# Pico_Audio_v0_20.net
KiCad netlist of a schematic drawn in EAGLE
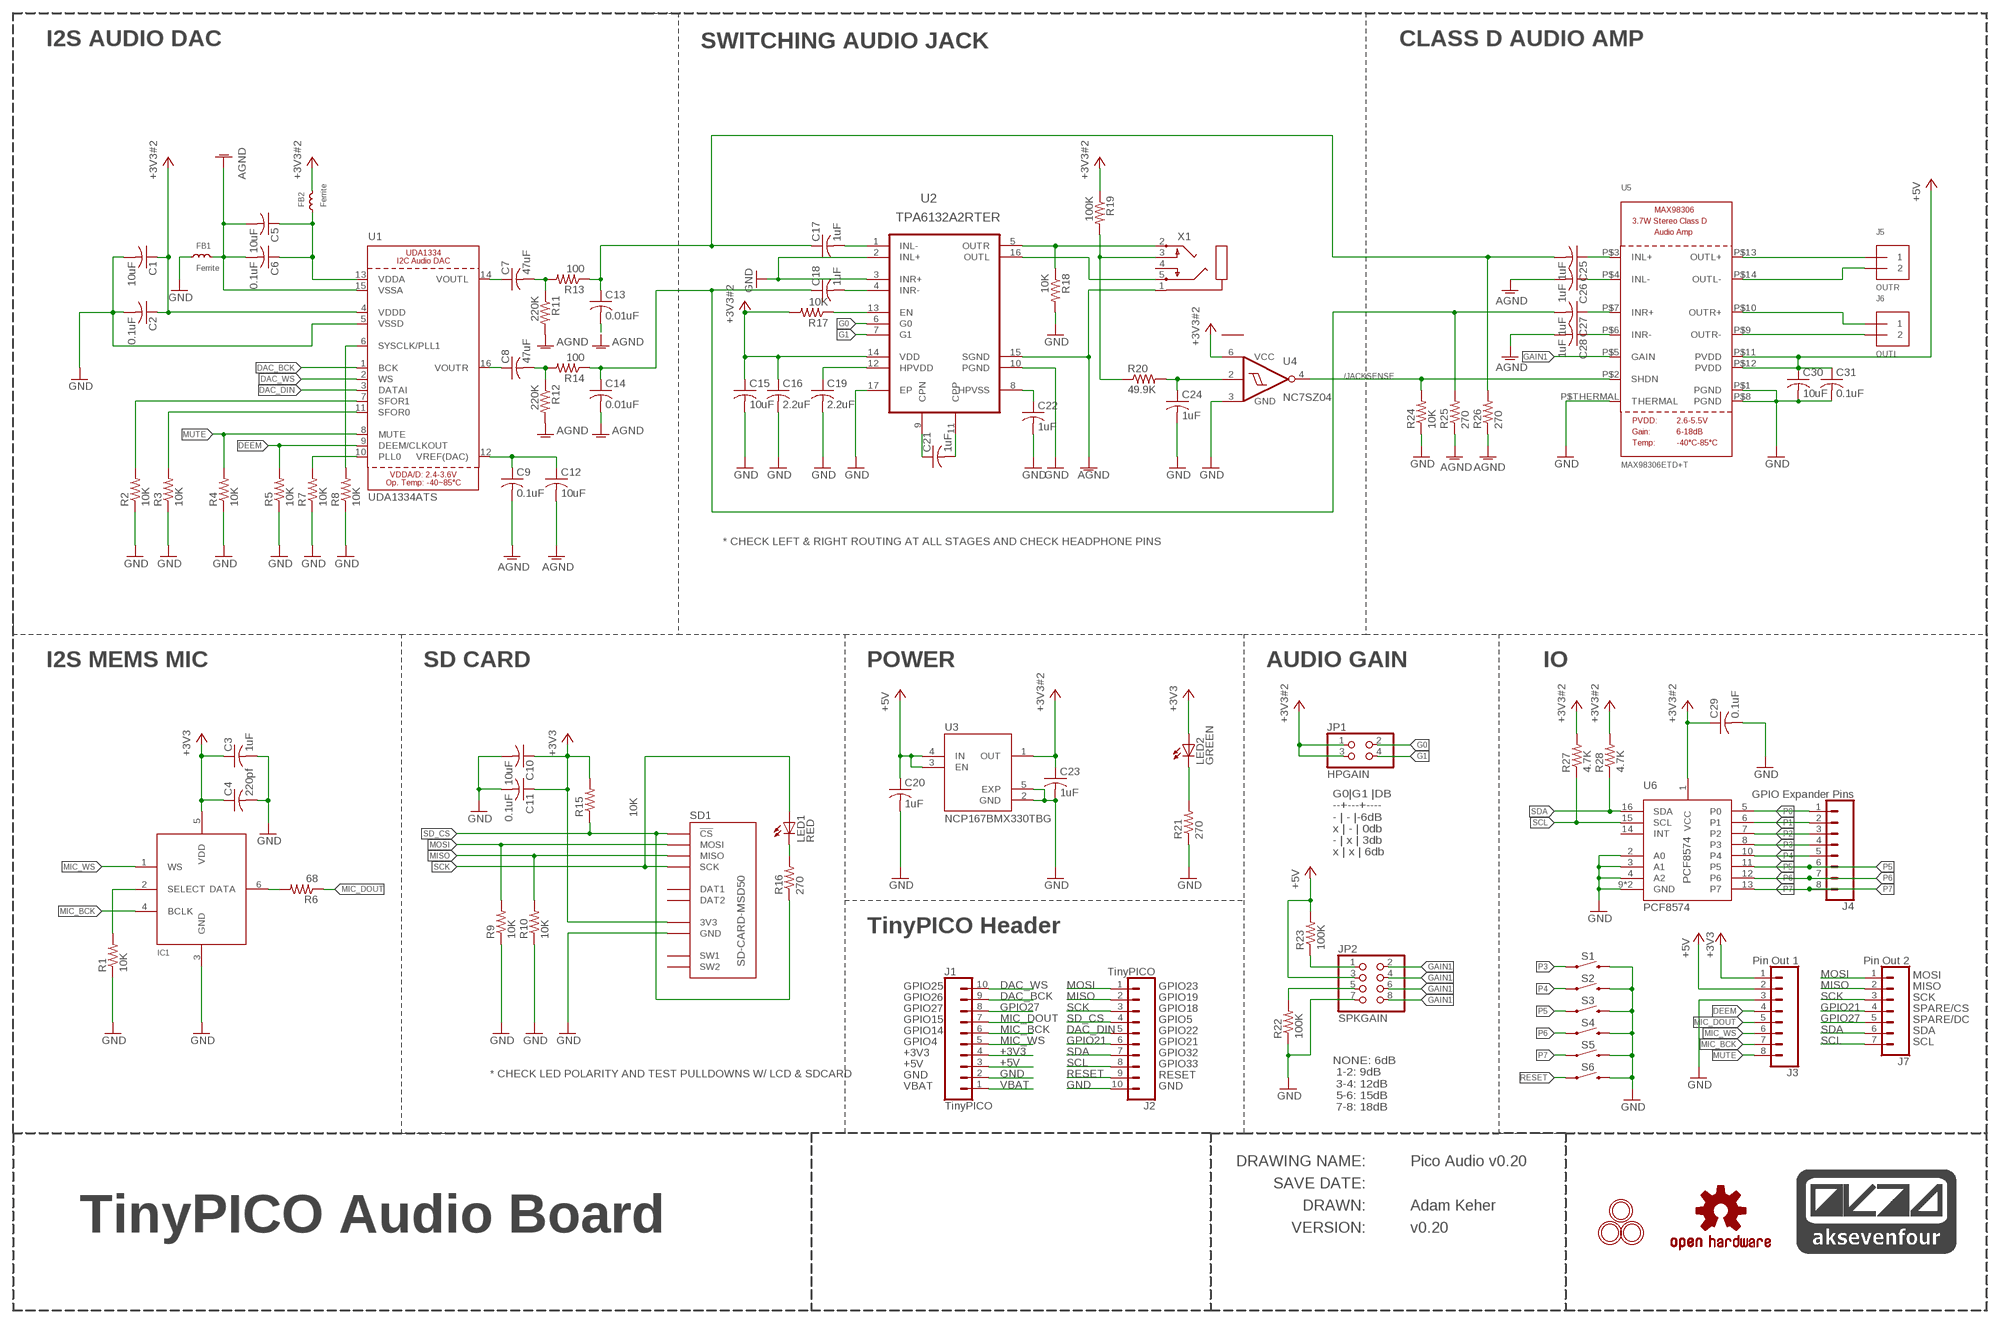
[diagram p0: schematic, sheet 1]

(export (version "E")
  (design (tool "Eeschema 10.0.6"))
  (components
    (comp (ref "AK74LOGO1")
      (value "AK74_LOGOAK74_LOGO_SMALL")
      (footprint "eagle-import:AK74_LOGO_MEDIUM")
      (libsource (lib "eagle-import") (part "AK74_LOGOAK74_LOGO_SMALL"))
    )
    (comp (ref "C1")
      (value "10uF")
      (footprint "eagle-import:C0603K")
      (libsource (lib "eagle-import") (part "C-USC0603K"))
    )
    (comp (ref "C2")
      (value "0.1uF")
      (footprint "eagle-import:C0402K")
      (libsource (lib "eagle-import") (part "C-USC0402K"))
    )
    (comp (ref "C3")
      (value "1uF")
      (footprint "eagle-import:C0402K")
      (libsource (lib "eagle-import") (part "C-USC0402K"))
    )
    (comp (ref "C4")
      (value "220pf")
      (footprint "eagle-import:C0402K")
      (libsource (lib "eagle-import") (part "C-USC0402K"))
    )
    (comp (ref "C5")
      (value "10uF")
      (footprint "eagle-import:C0603K")
      (libsource (lib "eagle-import") (part "C-USC0603K"))
    )
    (comp (ref "C6")
      (value "0.1uF")
      (footprint "eagle-import:C0402K")
      (libsource (lib "eagle-import") (part "C-USC0402K"))
    )
    (comp (ref "C7")
      (value "47uF")
      (footprint "eagle-import:C1210K")
      (libsource (lib "eagle-import") (part "C-USC1210K"))
    )
    (comp (ref "C8")
      (value "47uF")
      (footprint "eagle-import:C1210K")
      (libsource (lib "eagle-import") (part "C-USC1210K"))
    )
    (comp (ref "C9")
      (value "0.1uF")
      (footprint "eagle-import:C0402K")
      (libsource (lib "eagle-import") (part "C-USC0402K"))
    )
    (comp (ref "C10")
      (value "10uF")
      (footprint "eagle-import:C0603K")
      (libsource (lib "eagle-import") (part "C-USC0603K"))
    )
    (comp (ref "C11")
      (value "0.1uF")
      (footprint "eagle-import:C0402K")
      (libsource (lib "eagle-import") (part "C-USC0402K"))
    )
    (comp (ref "C12")
      (value "10uF")
      (footprint "eagle-import:C0603K")
      (libsource (lib "eagle-import") (part "C-USC0603K"))
    )
    (comp (ref "C13")
      (value "0.01uF")
      (footprint "eagle-import:C0402K")
      (libsource (lib "eagle-import") (part "C-USC0402K"))
    )
    (comp (ref "C14")
      (value "0.01uF")
      (footprint "eagle-import:C0402K")
      (libsource (lib "eagle-import") (part "C-USC0402K"))
    )
    (comp (ref "C15")
      (value "10uF")
      (footprint "eagle-import:C0603K")
      (libsource (lib "eagle-import") (part "C-USC0603K"))
    )
    (comp (ref "C16")
      (value "2.2uF")
      (footprint "eagle-import:C0402K")
      (libsource (lib "eagle-import") (part "C-USC0402K"))
    )
    (comp (ref "C17")
      (value "1uF")
      (footprint "eagle-import:C0402K")
      (libsource (lib "eagle-import") (part "C-USC0402K"))
    )
    (comp (ref "C18")
      (value "1uF")
      (footprint "eagle-import:C0402K")
      (libsource (lib "eagle-import") (part "C-USC0402K"))
    )
    (comp (ref "C19")
      (value "2.2uF")
      (footprint "eagle-import:C0402K")
      (libsource (lib "eagle-import") (part "C-USC0402K"))
    )
    (comp (ref "C20")
      (value "1uF")
      (footprint "eagle-import:C0402K")
      (libsource (lib "eagle-import") (part "C-USC0402K"))
    )
    (comp (ref "C21")
      (value "1uF")
      (footprint "eagle-import:C0402K")
      (libsource (lib "eagle-import") (part "C-USC0402K"))
    )
    (comp (ref "C22")
      (value "1uF")
      (footprint "eagle-import:C0402K")
      (libsource (lib "eagle-import") (part "C-USC0402K"))
    )
    (comp (ref "C23")
      (value "1uF")
      (footprint "eagle-import:C0402K")
      (libsource (lib "eagle-import") (part "C-USC0402K"))
    )
    (comp (ref "C24")
      (value "1uF")
      (footprint "eagle-import:C0402K")
      (libsource (lib "eagle-import") (part "C-USC0402K"))
    )
    (comp (ref "C25")
      (value "1uF")
      (footprint "eagle-import:C0402K")
      (libsource (lib "eagle-import") (part "C-USC0402K"))
    )
    (comp (ref "C26")
      (value "1uF")
      (footprint "eagle-import:C0402K")
      (libsource (lib "eagle-import") (part "C-USC0402K"))
    )
    (comp (ref "C27")
      (value "1uF")
      (footprint "eagle-import:C0402K")
      (libsource (lib "eagle-import") (part "C-USC0402K"))
    )
    (comp (ref "C28")
      (value "1uF")
      (footprint "eagle-import:C0402K")
      (libsource (lib "eagle-import") (part "C-USC0402K"))
    )
    (comp (ref "C29")
      (value "0.1uF")
      (footprint "eagle-import:C0402K")
      (libsource (lib "eagle-import") (part "C-USC0402K"))
    )
    (comp (ref "C30")
      (value "10uF")
      (footprint "eagle-import:C0603K")
      (libsource (lib "eagle-import") (part "C-USC0603K"))
    )
    (comp (ref "C31")
      (value "0.1uF")
      (footprint "eagle-import:C0402K")
      (libsource (lib "eagle-import") (part "C-USC0402K"))
    )
    (comp (ref "FB1")
      (value "Ferrite")
      (footprint "eagle-import:R0805")
      (libsource (lib "eagle-import") (part "FERRITEL0805"))
    )
    (comp (ref "FB2")
      (value "Ferrite")
      (footprint "eagle-import:R0805")
      (libsource (lib "eagle-import") (part "FERRITEL0805"))
    )
    (comp (ref "IC1")
      (value "MIC_I2S_SPH0645")
      (footprint "eagle-import:SPH0645LM4H")
      (libsource (lib "eagle-import") (part "MIC_I2S_SPH0645"))
    )
    (comp (ref "J1")
      (value "TinyPICO")
      (footprint "eagle-import:1X10_NO_SILK")
      (libsource (lib "eagle-import") (part "TINYPICO_HEADER_10NO_SILK_PTH_FEMALE"))
    )
    (comp (ref "J2")
      (value "TinyPICO")
      (footprint "eagle-import:1X10_NO_SILK")
      (libsource (lib "eagle-import") (part "TINYPICO_HEADER_10NO_SILK_PTH_FEMALE"))
    )
    (comp (ref "J3")
      (value "Pin Out 1")
      (footprint "eagle-import:1X08_NO_SILK")
      (libsource (lib "eagle-import") (part "CONN_08NO_SILK_FEMALE_PTH"))
    )
    (comp (ref "J4")
      (value "GPIO Expander Pins")
      (footprint "eagle-import:1X08_NO_SILK")
      (libsource (lib "eagle-import") (part "CONN_08NO_SILK_FEMALE_PTH"))
    )
    (comp (ref "J5")
      (value "OUTR")
      (footprint "eagle-import:TERMBLOCK_1X2-3.5MM")
      (libsource (lib "eagle-import") (part "TERMBLOCK_1X2"))
    )
    (comp (ref "J6")
      (value "OUTL")
      (footprint "eagle-import:TERMBLOCK_1X2-3.5MM")
      (libsource (lib "eagle-import") (part "TERMBLOCK_1X2"))
    )
    (comp (ref "J7")
      (value "Pin Out 2")
      (footprint "eagle-import:1X07_NO_SILK")
      (libsource (lib "eagle-import") (part "CONN_07NO_SILK"))
    )
    (comp (ref "JP1")
      (value "HPGAIN")
      (footprint "eagle-import:2X02")
      (libsource (lib "eagle-import") (part "PINHD-2X2"))
    )
    (comp (ref "JP2")
      (value "SPKGAIN")
      (footprint "eagle-import:2X04")
      (libsource (lib "eagle-import") (part "PINHD-2X4"))
    )
    (comp (ref "LED1")
      (value "RED")
      (footprint "eagle-import:CHIP-LED0805")
      (libsource (lib "eagle-import") (part "LEDCHIP-LED0805"))
    )
    (comp (ref "LED2")
      (value "GREEN")
      (footprint "eagle-import:CHIP-LED0805")
      (libsource (lib "eagle-import") (part "LEDCHIP-LED0805"))
    )
    (comp (ref "LOGO1")
      (value "OSHW-LOGOM")
      (footprint "eagle-import:OSHW-LOGO-M")
      (libsource (lib "eagle-import") (part "OSHW-LOGOM"))
    )
    (comp (ref "MH1")
      (value "MOUNTINGHOLE2.5")
      (footprint "eagle-import:MOUNTINGHOLE_2.5_PLATED")
      (libsource (lib "eagle-import") (part "MOUNTINGHOLE2.5"))
    )
    (comp (ref "MH2")
      (value "MOUNTINGHOLE2.5")
      (footprint "eagle-import:MOUNTINGHOLE_2.5_PLATED")
      (libsource (lib "eagle-import") (part "MOUNTINGHOLE2.5"))
    )
    (comp (ref "MH3")
      (value "MOUNTINGHOLE2.5")
      (footprint "eagle-import:MOUNTINGHOLE_2.5_PLATED")
      (libsource (lib "eagle-import") (part "MOUNTINGHOLE2.5"))
    )
    (comp (ref "R1")
      (value "10K")
      (footprint "eagle-import:R0402")
      (libsource (lib "eagle-import") (part "R-US_R0402"))
    )
    (comp (ref "R2")
      (value "10K")
      (footprint "eagle-import:R0402")
      (libsource (lib "eagle-import") (part "R-US_R0402"))
    )
    (comp (ref "R3")
      (value "10K")
      (footprint "eagle-import:R0402")
      (libsource (lib "eagle-import") (part "R-US_R0402"))
    )
    (comp (ref "R4")
      (value "10K")
      (footprint "eagle-import:R0402")
      (libsource (lib "eagle-import") (part "R-US_R0402"))
    )
    (comp (ref "R5")
      (value "10K")
      (footprint "eagle-import:R0402")
      (libsource (lib "eagle-import") (part "R-US_R0402"))
    )
    (comp (ref "R6")
      (value "68")
      (footprint "eagle-import:R0402")
      (libsource (lib "eagle-import") (part "R-US_R0402"))
    )
    (comp (ref "R7")
      (value "10K")
      (footprint "eagle-import:R0402")
      (libsource (lib "eagle-import") (part "R-US_R0402"))
    )
    (comp (ref "R8")
      (value "10K")
      (footprint "eagle-import:R0402")
      (libsource (lib "eagle-import") (part "R-US_R0402"))
    )
    (comp (ref "R9")
      (value "10K")
      (footprint "eagle-import:R0402")
      (libsource (lib "eagle-import") (part "R-US_R0402"))
    )
    (comp (ref "R10")
      (value "10K")
      (footprint "eagle-import:R0402")
      (libsource (lib "eagle-import") (part "R-US_R0402"))
    )
    (comp (ref "R11")
      (value "220K")
      (footprint "eagle-import:R0402")
      (libsource (lib "eagle-import") (part "R-US_R0402"))
    )
    (comp (ref "R12")
      (value "220K")
      (footprint "eagle-import:R0402")
      (libsource (lib "eagle-import") (part "R-US_R0402"))
    )
    (comp (ref "R13")
      (value "100")
      (footprint "eagle-import:R0402")
      (libsource (lib "eagle-import") (part "R-US_R0402"))
    )
    (comp (ref "R14")
      (value "100")
      (footprint "eagle-import:R0402")
      (libsource (lib "eagle-import") (part "R-US_R0402"))
    )
    (comp (ref "R15")
      (value "10K")
      (footprint "eagle-import:R0402")
      (libsource (lib "eagle-import") (part "R-US_R0402"))
    )
    (comp (ref "R16")
      (value "270")
      (footprint "eagle-import:R0402")
      (libsource (lib "eagle-import") (part "R-US_R0402"))
    )
    (comp (ref "R17")
      (value "10K")
      (footprint "eagle-import:R0402")
      (libsource (lib "eagle-import") (part "R-US_R0402"))
    )
    (comp (ref "R18")
      (value "10K")
      (footprint "eagle-import:R0402")
      (libsource (lib "eagle-import") (part "R-US_R0402"))
    )
    (comp (ref "R19")
      (value "100K")
      (footprint "eagle-import:R0402")
      (libsource (lib "eagle-import") (part "R-US_R0402"))
    )
    (comp (ref "R20")
      (value "49.9K")
      (footprint "eagle-import:R0402")
      (libsource (lib "eagle-import") (part "R-US_R0402"))
    )
    (comp (ref "R21")
      (value "270")
      (footprint "eagle-import:R0402")
      (libsource (lib "eagle-import") (part "R-US_R0402"))
    )
    (comp (ref "R22")
      (value "100K")
      (footprint "eagle-import:R0402")
      (libsource (lib "eagle-import") (part "R-US_R0402"))
    )
    (comp (ref "R23")
      (value "100K")
      (footprint "eagle-import:R0402")
      (libsource (lib "eagle-import") (part "R-US_R0402"))
    )
    (comp (ref "R24")
      (value "10K")
      (footprint "eagle-import:R0402")
      (libsource (lib "eagle-import") (part "R-US_R0402"))
    )
    (comp (ref "R25")
      (value "270")
      (footprint "eagle-import:R0402")
      (libsource (lib "eagle-import") (part "R-US_R0402"))
    )
    (comp (ref "R26")
      (value "270")
      (footprint "eagle-import:R0402")
      (libsource (lib "eagle-import") (part "R-US_R0402"))
    )
    (comp (ref "R27")
      (value "4.7K")
      (footprint "eagle-import:R0402")
      (libsource (lib "eagle-import") (part "R-US_R0402"))
    )
    (comp (ref "R28")
      (value "4.7K")
      (footprint "eagle-import:R0402")
      (libsource (lib "eagle-import") (part "R-US_R0402"))
    )
    (comp (ref "S1")
      (value "SKSCLDE010")
      (footprint "eagle-import:SKSCLDE010")
      (libsource (lib "eagle-import") (part "SKSCLDE010"))
    )
    (comp (ref "S2")
      (value "SKSCLDE010")
      (footprint "eagle-import:SKSCLDE010")
      (libsource (lib "eagle-import") (part "SKSCLDE010"))
    )
    (comp (ref "S3")
      (value "SKSCLDE010")
      (footprint "eagle-import:SKSCLDE010")
      (libsource (lib "eagle-import") (part "SKSCLDE010"))
    )
    (comp (ref "S4")
      (value "SKSCLDE010")
      (footprint "eagle-import:SKSCLDE010")
      (libsource (lib "eagle-import") (part "SKSCLDE010"))
    )
    (comp (ref "S5")
      (value "SKSCLDE010")
      (footprint "eagle-import:SKSCLDE010")
      (libsource (lib "eagle-import") (part "SKSCLDE010"))
    )
    (comp (ref "S6")
      (value "MOMENTARY-SWITCH-SPST-SMD-4.6X2.8MM")
      (footprint "eagle-import:TACTILE_SWITCH_SMD_4.6X2.8MM")
      (libsource (lib "eagle-import") (part "MOMENTARY-SWITCH-SPST-SMD-4.6X2.8MM"))
    )
    (comp (ref "SD1")
      (value "SD-CARD-MSD50")
      (footprint "eagle-import:SD_5031821853")
      (libsource (lib "eagle-import") (part "SD-CARD-MSD50"))
    )
    (comp (ref "U1")
      (value "UDA1334ATS")
      (footprint "eagle-import:SSOP16_4.4MM")
      (libsource (lib "eagle-import") (part "AUDIO_I2S_UDA1334{dblquote}{dblquote}"))
    )
    (comp (ref "U2")
      (value "TPA6132A2RTER")
      (footprint "eagle-import:QFN50P300X300X80-16N")
      (fields (field (name "MF") "Texas Instruments"))
      (libsource (lib "eagle-import") (part "TPA6132A2RTER"))
    )
    (comp (ref "U3")
      (value "NCP170AMX300TCG")
      (footprint "eagle-import:VREG_NCP170AMX300TCG")
      (fields (field (name "MF") "ON Semiconductor"))
      (libsource (lib "eagle-import") (part "NCP170AMX300TCG"))
    )
    (comp (ref "U4")
      (value "NC7SZ04")
      (footprint "eagle-import:MICROPAK-6")
      (libsource (lib "eagle-import") (part "NC7SZ04"))
    )
    (comp (ref "U5")
      (value "MAX98306ETD+T")
      (footprint "eagle-import:TDFN14_3X3MM")
      (libsource (lib "eagle-import") (part "AUDIOAMP_MAX98306"))
    )
    (comp (ref "U6")
      (value "PCF8574")
      (footprint "eagle-import:QFN-16-3MM")
      (libsource (lib "eagle-import") (part "PCF8574"))
    )
    (comp (ref "X1")
      (value "STEREOJACKSTX3120-5B")
      (footprint "eagle-import:STX3100")
      (libsource (lib "eagle-import") (part "STEREOJACKSTX3120-5B"))
    )
  )
  (nets
    (net (code "1") (name "+3V3") (class "Default")
      (node (ref "C10") (pin "1") (pinfunction "1_1") (pintype "passive"))
      (node (ref "C11") (pin "1") (pinfunction "1_1") (pintype "passive"))
      (node (ref "C3") (pin "1") (pinfunction "1_1") (pintype "passive"))
      (node (ref "C4") (pin "1") (pinfunction "1_1") (pintype "passive"))
      (node (ref "IC1") (pin "5") (pinfunction "VDD_5") (pintype "power_in"))
      (node (ref "J1") (pin "4") (pinfunction "4_4") (pintype "passive"))
      (node (ref "J3") (pin "1") (pinfunction "1_1") (pintype "passive"))
      (node (ref "LED2") (pin "A") (pinfunction "A_A") (pintype "passive"))
      (node (ref "R15") (pin "2") (pinfunction "2_2") (pintype "passive"))
      (node (ref "SD1") (pin "VCC") (pinfunction "3V3_VCC") (pintype "bidirectional"))
    )
    (net (code "2") (name "+3V3#2") (class "Default")
      (node (ref "C1") (pin "1") (pinfunction "1_1") (pintype "passive"))
      (node (ref "C15") (pin "1") (pinfunction "1_1") (pintype "passive"))
      (node (ref "C16") (pin "1") (pinfunction "1_1") (pintype "passive"))
      (node (ref "C2") (pin "1") (pinfunction "1_1") (pintype "passive"))
      (node (ref "C23") (pin "1") (pinfunction "1_1") (pintype "passive"))
      (node (ref "C29") (pin "1") (pinfunction "1_1") (pintype "passive"))
      (node (ref "FB2") (pin "2") (pinfunction "2_2") (pintype "passive"))
      (node (ref "JP1") (pin "1") (pinfunction "1_1") (pintype "passive"))
      (node (ref "JP1") (pin "3") (pinfunction "3_3") (pintype "passive"))
      (node (ref "R17") (pin "2") (pinfunction "2_2") (pintype "passive"))
      (node (ref "R19") (pin "1") (pinfunction "1_1") (pintype "passive"))
      (node (ref "R27") (pin "2") (pinfunction "2_2") (pintype "passive"))
      (node (ref "R28") (pin "2") (pinfunction "2_2") (pintype "passive"))
      (node (ref "U1") (pin "4") (pinfunction "VDDD_4") (pintype "power_in"))
      (node (ref "U2") (pin "14") (pinfunction "VDD_14") (pintype "power_in"))
      (node (ref "U3") (pin "1") (pinfunction "OUT_1") (pintype "output"))
      (node (ref "U4") (pin "6") (pinfunction "VCC_6") (pintype "power_in"))
      (node (ref "U6") (pin "1") (pinfunction "VCC_1") (pintype "bidirectional"))
    )
    (net (code "3") (name "+5V") (class "Default")
      (node (ref "C20") (pin "1") (pinfunction "1_1") (pintype "passive"))
      (node (ref "C30") (pin "1") (pinfunction "1_1") (pintype "passive"))
      (node (ref "C31") (pin "1") (pinfunction "1_1") (pintype "passive"))
      (node (ref "J1") (pin "3") (pinfunction "3_3") (pintype "passive"))
      (node (ref "J3") (pin "2") (pinfunction "2_2") (pintype "passive"))
      (node (ref "JP2") (pin "3") (pinfunction "3_3") (pintype "passive"))
      (node (ref "R23") (pin "2") (pinfunction "2_2") (pintype "passive"))
      (node (ref "U3") (pin "3") (pinfunction "EN_3") (pintype "input"))
      (node (ref "U3") (pin "4") (pinfunction "IN_4") (pintype "input"))
      (node (ref "U5") (pin "P$11") (pinfunction "PVDD_P$11") (pintype "power_in"))
      (node (ref "U5") (pin "P$12") (pinfunction "PVDD_P$12") (pintype "power_in"))
    )
    (net (code "4") (name "/GPIO21") (class "Default")
      (node (ref "J2") (pin "6") (pinfunction "6_6") (pintype "passive"))
      (node (ref "J7") (pin "4") (pinfunction "4_4") (pintype "passive"))
    )
    (net (code "5") (name "/GPIO27") (class "Default")
      (node (ref "J1") (pin "8") (pinfunction "8_8") (pintype "passive"))
      (node (ref "J7") (pin "5") (pinfunction "5_5") (pintype "passive"))
    )
    (net (code "6") (name "/VBAT") (class "Default")
      (node (ref "J1") (pin "1") (pinfunction "1_1") (pintype "passive"))
    )
    (net (code "7") (name "/{slash}JACKSENSE") (class "Default")
      (node (ref "R24") (pin "2") (pinfunction "2_2") (pintype "passive"))
      (node (ref "U4") (pin "4") (pinfunction "Y_4") (pintype "output"))
      (node (ref "U5") (pin "P$2") (pinfunction "SHDN_P$2") (pintype "input"))
    )
    (net (code "8") (name "AGND") (class "Default")
      (node (ref "C12") (pin "2") (pinfunction "2_2") (pintype "passive"))
      (node (ref "C13") (pin "2") (pinfunction "2_2") (pintype "passive"))
      (node (ref "C14") (pin "2") (pinfunction "2_2") (pintype "passive"))
      (node (ref "C26") (pin "2") (pinfunction "2_2") (pintype "passive"))
      (node (ref "C28") (pin "2") (pinfunction "2_2") (pintype "passive"))
      (node (ref "C5") (pin "2") (pinfunction "2_2") (pintype "passive"))
      (node (ref "C6") (pin "2") (pinfunction "2_2") (pintype "passive"))
      (node (ref "C9") (pin "2") (pinfunction "2_2") (pintype "passive"))
      (node (ref "FB1") (pin "2") (pinfunction "2_2") (pintype "passive"))
      (node (ref "R11") (pin "2") (pinfunction "2_2") (pintype "passive"))
      (node (ref "R12") (pin "2") (pinfunction "2_2") (pintype "passive"))
      (node (ref "R25") (pin "1") (pinfunction "1_1") (pintype "passive"))
      (node (ref "R26") (pin "1") (pinfunction "1_1") (pintype "passive"))
      (node (ref "U1") (pin "15") (pinfunction "VSSA_15") (pintype "power_in"))
      (node (ref "U2") (pin "15") (pinfunction "SGND_15") (pintype "passive"))
      (node (ref "X1") (pin "1") (pinfunction "1_1") (pintype "passive"))
    )
    (net (code "9") (name "DAC_BCK") (class "Default")
      (node (ref "J1") (pin "9") (pinfunction "9_9") (pintype "passive"))
      (node (ref "U1") (pin "1") (pinfunction "BCK_1") (pintype "input"))
    )
    (net (code "10") (name "DAC_DIN") (class "Default")
      (node (ref "J2") (pin "5") (pinfunction "5_5") (pintype "passive"))
      (node (ref "U1") (pin "3") (pinfunction "DATAI_3") (pintype "input"))
    )
    (net (code "11") (name "DAC_WS") (class "Default")
      (node (ref "J1") (pin "10") (pinfunction "10_10") (pintype "passive"))
      (node (ref "U1") (pin "2") (pinfunction "WS_2") (pintype "input"))
    )
    (net (code "12") (name "DEEM") (class "Default")
      (node (ref "J3") (pin "4") (pinfunction "4_4") (pintype "passive"))
      (node (ref "R5") (pin "2") (pinfunction "2_2") (pintype "passive"))
      (node (ref "U1") (pin "9") (pinfunction "DEEM/CLKOUT_9") (pintype "bidirectional"))
    )
    (net (code "13") (name "G0") (class "Default")
      (node (ref "JP1") (pin "2") (pinfunction "2_2") (pintype "passive"))
      (node (ref "U2") (pin "6") (pinfunction "G0_6") (pintype "input"))
    )
    (net (code "14") (name "G1") (class "Default")
      (node (ref "JP1") (pin "4") (pinfunction "4_4") (pintype "passive"))
      (node (ref "U2") (pin "7") (pinfunction "G1_7") (pintype "input"))
    )
    (net (code "15") (name "GAIN1") (class "Default")
      (node (ref "JP2") (pin "2") (pinfunction "2_2") (pintype "passive"))
      (node (ref "JP2") (pin "4") (pinfunction "4_4") (pintype "passive"))
      (node (ref "JP2") (pin "6") (pinfunction "6_6") (pintype "passive"))
      (node (ref "JP2") (pin "8") (pinfunction "8_8") (pintype "passive"))
      (node (ref "U5") (pin "P$5") (pinfunction "GAIN_P$5") (pintype "input"))
    )
    (net (code "16") (name "GND") (class "Default")
      (node (ref "C1") (pin "2") (pinfunction "2_2") (pintype "passive"))
      (node (ref "C10") (pin "2") (pinfunction "2_2") (pintype "passive"))
      (node (ref "C11") (pin "2") (pinfunction "2_2") (pintype "passive"))
      (node (ref "C15") (pin "2") (pinfunction "2_2") (pintype "passive"))
      (node (ref "C16") (pin "2") (pinfunction "2_2") (pintype "passive"))
      (node (ref "C19") (pin "2") (pinfunction "2_2") (pintype "passive"))
      (node (ref "C2") (pin "2") (pinfunction "2_2") (pintype "passive"))
      (node (ref "C20") (pin "2") (pinfunction "2_2") (pintype "passive"))
      (node (ref "C22") (pin "2") (pinfunction "2_2") (pintype "passive"))
      (node (ref "C23") (pin "2") (pinfunction "2_2") (pintype "passive"))
      (node (ref "C24") (pin "2") (pinfunction "2_2") (pintype "passive"))
      (node (ref "C29") (pin "2") (pinfunction "2_2") (pintype "passive"))
      (node (ref "C3") (pin "2") (pinfunction "2_2") (pintype "passive"))
      (node (ref "C30") (pin "2") (pinfunction "2_2") (pintype "passive"))
      (node (ref "C31") (pin "2") (pinfunction "2_2") (pintype "passive"))
      (node (ref "C4") (pin "2") (pinfunction "2_2") (pintype "passive"))
      (node (ref "FB1") (pin "1") (pinfunction "1_1") (pintype "passive"))
      (node (ref "IC1") (pin "3") (pinfunction "GND_3") (pintype "power_in"))
      (node (ref "J1") (pin "2") (pinfunction "2_2") (pintype "passive"))
      (node (ref "J2") (pin "10") (pinfunction "10_10") (pintype "passive"))
      (node (ref "J3") (pin "3") (pinfunction "3_3") (pintype "passive"))
      (node (ref "JP2") (pin "7") (pinfunction "7_7") (pintype "passive"))
      (node (ref "R1") (pin "1") (pinfunction "1_1") (pintype "passive"))
      (node (ref "R10") (pin "1") (pinfunction "1_1") (pintype "passive"))
      (node (ref "R18") (pin "2") (pinfunction "2_2") (pintype "passive"))
      (node (ref "R2") (pin "1") (pinfunction "1_1") (pintype "passive"))
      (node (ref "R21") (pin "1") (pinfunction "1_1") (pintype "passive"))
      (node (ref "R22") (pin "1") (pinfunction "1_1") (pintype "passive"))
      (node (ref "R24") (pin "1") (pinfunction "1_1") (pintype "passive"))
      (node (ref "R3") (pin "1") (pinfunction "1_1") (pintype "passive"))
      (node (ref "R4") (pin "1") (pinfunction "1_1") (pintype "passive"))
      (node (ref "R5") (pin "1") (pinfunction "1_1") (pintype "passive"))
      (node (ref "R7") (pin "1") (pinfunction "1_1") (pintype "passive"))
      (node (ref "R8") (pin "1") (pinfunction "1_1") (pintype "passive"))
      (node (ref "R9") (pin "1") (pinfunction "1_1") (pintype "passive"))
      (node (ref "S1") (pin "3") (pinfunction "2_3") (pintype "passive"))
      (node (ref "S1") (pin "4") (pinfunction "2_4") (pintype "passive"))
      (node (ref "S2") (pin "3") (pinfunction "2_3") (pintype "passive"))
      (node (ref "S2") (pin "4") (pinfunction "2_4") (pintype "passive"))
      (node (ref "S3") (pin "3") (pinfunction "2_3") (pintype "passive"))
      (node (ref "S3") (pin "4") (pinfunction "2_4") (pintype "passive"))
      (node (ref "S4") (pin "3") (pinfunction "2_3") (pintype "passive"))
      (node (ref "S4") (pin "4") (pinfunction "2_4") (pintype "passive"))
      (node (ref "S5") (pin "3") (pinfunction "2_3") (pintype "passive"))
      (node (ref "S5") (pin "4") (pinfunction "2_4") (pintype "passive"))
      (node (ref "S6") (pin "3") (pinfunction "2_3") (pintype "passive"))
      (node (ref "S6") (pin "4") (pinfunction "2_4") (pintype "passive"))
      (node (ref "SD1") (pin "GND") (pinfunction "GND_GND") (pintype "bidirectional"))
      (node (ref "U1") (pin "5") (pinfunction "VSSD_5") (pintype "power_in"))
      (node (ref "U2") (pin "10") (pinfunction "PGND_10") (pintype "passive"))
      (node (ref "U2") (pin "17") (pinfunction "EP_17") (pintype "passive"))
      (node (ref "U2") (pin "2") (pinfunction "INL+_2") (pintype "input"))
      (node (ref "U2") (pin "3") (pinfunction "INR+_3") (pintype "input"))
      (node (ref "U3") (pin "2") (pinfunction "GND_2") (pintype "power_in"))
      (node (ref "U3") (pin "5") (pinfunction "EXP_5") (pintype "power_in"))
      (node (ref "U4") (pin "3") (pinfunction "GND_3") (pintype "power_in"))
      (node (ref "U5") (pin "P$1") (pinfunction "PGND_P$1") (pintype "power_in"))
      (node (ref "U5") (pin "P$8") (pinfunction "PGND_P$8") (pintype "power_in"))
      (node (ref "U5") (pin "P$THERMAL") (pinfunction "THERMAL_P$THERMAL") (pintype "power_in"))
      (node (ref "U6") (pin "2") (pinfunction "A0_2") (pintype "bidirectional"))
      (node (ref "U6") (pin "3") (pinfunction "A1_3") (pintype "bidirectional"))
      (node (ref "U6") (pin "4") (pinfunction "A2_4") (pintype "bidirectional"))
      (node (ref "U6") (pin "9") (pinfunction "GND_9") (pintype "bidirectional"))
      (node (ref "U6") (pin "P$1") (pinfunction "GND_P$1") (pintype "bidirectional"))
    )
    (net (code "17") (name "MIC_BCK") (class "Default")
      (node (ref "IC1") (pin "4") (pinfunction "BCLK_4") (pintype "input"))
      (node (ref "J1") (pin "6") (pinfunction "6_6") (pintype "passive"))
      (node (ref "J3") (pin "7") (pinfunction "7_7") (pintype "passive"))
    )
    (net (code "18") (name "MIC_DOUT") (class "Default")
      (node (ref "J1") (pin "7") (pinfunction "7_7") (pintype "passive"))
      (node (ref "J3") (pin "5") (pinfunction "5_5") (pintype "passive"))
      (node (ref "R6") (pin "1") (pinfunction "1_1") (pintype "passive"))
    )
    (net (code "19") (name "MIC_WS") (class "Default")
      (node (ref "IC1") (pin "1") (pinfunction "WS_1") (pintype "input"))
      (node (ref "J1") (pin "5") (pinfunction "5_5") (pintype "passive"))
      (node (ref "J3") (pin "6") (pinfunction "6_6") (pintype "passive"))
    )
    (net (code "20") (name "MISO") (class "Default")
      (node (ref "J2") (pin "2") (pinfunction "2_2") (pintype "passive"))
      (node (ref "J7") (pin "2") (pinfunction "2_2") (pintype "passive"))
      (node (ref "R10") (pin "2") (pinfunction "2_2") (pintype "passive"))
      (node (ref "SD1") (pin "MISO") (pinfunction "MISO_MISO") (pintype "bidirectional"))
    )
    (net (code "21") (name "MOSI") (class "Default")
      (node (ref "J2") (pin "1") (pinfunction "1_1") (pintype "passive"))
      (node (ref "J7") (pin "1") (pinfunction "1_1") (pintype "passive"))
      (node (ref "R9") (pin "2") (pinfunction "2_2") (pintype "passive"))
      (node (ref "SD1") (pin "MOSI") (pinfunction "MOSI_MOSI") (pintype "bidirectional"))
    )
    (net (code "22") (name "MUTE") (class "Default")
      (node (ref "J3") (pin "8") (pinfunction "8_8") (pintype "passive"))
      (node (ref "R4") (pin "2") (pinfunction "2_2") (pintype "passive"))
      (node (ref "U1") (pin "8") (pinfunction "MUTE_8") (pintype "input"))
    )
    (net (code "23") (name "Net-(C7-Pad2)") (class "Default")
      (node (ref "C7") (pin "2") (pinfunction "2_2") (pintype "passive"))
      (node (ref "R11") (pin "1") (pinfunction "1_1") (pintype "passive"))
      (node (ref "R13") (pin "2") (pinfunction "2_2") (pintype "passive"))
    )
    (net (code "24") (name "Net-(C8-Pad2)") (class "Default")
      (node (ref "C8") (pin "2") (pinfunction "2_2") (pintype "passive"))
      (node (ref "R12") (pin "1") (pinfunction "1_1") (pintype "passive"))
      (node (ref "R14") (pin "2") (pinfunction "2_2") (pintype "passive"))
    )
    (net (code "25") (name "Net-(C13-Pad1)") (class "Default")
      (node (ref "C13") (pin "1") (pinfunction "1_1") (pintype "passive"))
      (node (ref "C17") (pin "1") (pinfunction "1_1") (pintype "passive"))
      (node (ref "C25") (pin "2") (pinfunction "2_2") (pintype "passive"))
      (node (ref "R13") (pin "1") (pinfunction "1_1") (pintype "passive"))
      (node (ref "R26") (pin "2") (pinfunction "2_2") (pintype "passive"))
    )
    (net (code "26") (name "Net-(C14-Pad1)") (class "Default")
      (node (ref "C14") (pin "1") (pinfunction "1_1") (pintype "passive"))
      (node (ref "C18") (pin "1") (pinfunction "1_1") (pintype "passive"))
      (node (ref "C27") (pin "2") (pinfunction "2_2") (pintype "passive"))
      (node (ref "R14") (pin "1") (pinfunction "1_1") (pintype "passive"))
      (node (ref "R25") (pin "2") (pinfunction "2_2") (pintype "passive"))
    )
    (net (code "27") (name "Net-(IC1-DATA)") (class "Default")
      (node (ref "IC1") (pin "6") (pinfunction "DATA_6") (pintype "output"))
      (node (ref "R6") (pin "2") (pinfunction "2_2") (pintype "passive"))
    )
    (net (code "28") (name "Net-(IC1-SELECT)") (class "Default")
      (node (ref "IC1") (pin "2") (pinfunction "SELECT_2") (pintype "input"))
      (node (ref "R1") (pin "2") (pinfunction "2_2") (pintype "passive"))
    )
    (net (code "29") (name "Net-(JP2-Pad1)") (class "Default")
      (node (ref "JP2") (pin "1") (pinfunction "1_1") (pintype "passive"))
      (node (ref "R23") (pin "1") (pinfunction "1_1") (pintype "passive"))
    )
    (net (code "30") (name "Net-(JP2-Pad5)") (class "Default")
      (node (ref "JP2") (pin "5") (pinfunction "5_5") (pintype "passive"))
      (node (ref "R22") (pin "2") (pinfunction "2_2") (pintype "passive"))
    )
    (net (code "31") (name "Net-(LED1-PadC)") (class "Default")
      (node (ref "LED1") (pin "C") (pinfunction "C_C") (pintype "passive"))
      (node (ref "R16") (pin "2") (pinfunction "2_2") (pintype "passive"))
    )
    (net (code "32") (name "Net-(LED2-PadC)") (class "Default")
      (node (ref "LED2") (pin "C") (pinfunction "C_C") (pintype "passive"))
      (node (ref "R21") (pin "2") (pinfunction "2_2") (pintype "passive"))
    )
    (net (code "33") (name "Net-(R19-Pad2)") (class "Default")
      (node (ref "R19") (pin "2") (pinfunction "2_2") (pintype "passive"))
      (node (ref "R20") (pin "1") (pinfunction "1_1") (pintype "passive"))
      (node (ref "X1") (pin "3") (pinfunction "3_3") (pintype "passive"))
    )
    (net (code "34") (name "Net-(U1-PLL0)") (class "Default")
      (node (ref "R7") (pin "2") (pinfunction "2_2") (pintype "passive"))
      (node (ref "U1") (pin "10") (pinfunction "PLL0_10") (pintype "input"))
    )
    (net (code "35") (name "Net-(U1-SFOR0)") (class "Default")
      (node (ref "R3") (pin "2") (pinfunction "2_2") (pintype "passive"))
      (node (ref "U1") (pin "11") (pinfunction "SFOR0_11") (pintype "input"))
    )
    (net (code "36") (name "Net-(U1-SFOR1)") (class "Default")
      (node (ref "R2") (pin "2") (pinfunction "2_2") (pintype "passive"))
      (node (ref "U1") (pin "7") (pinfunction "SFOR1_7") (pintype "input"))
    )
    (net (code "37") (name "Net-(U1-SYSCLK{slash}PLL1)") (class "Default")
      (node (ref "R8") (pin "2") (pinfunction "2_2") (pintype "passive"))
      (node (ref "U1") (pin "6") (pinfunction "SYSCLK/PLL1_6") (pintype "input"))
    )
    (net (code "38") (name "Net-(U1-VDDA)") (class "Default")
      (node (ref "C5") (pin "1") (pinfunction "1_1") (pintype "passive"))
      (node (ref "C6") (pin "1") (pinfunction "1_1") (pintype "passive"))
      (node (ref "FB2") (pin "1") (pinfunction "1_1") (pintype "passive"))
      (node (ref "U1") (pin "13") (pinfunction "VDDA_13") (pintype "power_in"))
    )
    (net (code "39") (name "Net-(U1-VOUTL)") (class "Default")
      (node (ref "C7") (pin "1") (pinfunction "1_1") (pintype "passive"))
      (node (ref "U1") (pin "14") (pinfunction "VOUTL_14") (pintype "output"))
    )
    (net (code "40") (name "Net-(U1-VOUTR)") (class "Default")
      (node (ref "C8") (pin "1") (pinfunction "1_1") (pintype "passive"))
      (node (ref "U1") (pin "16") (pinfunction "VOUTR_16") (pintype "output"))
    )
    (net (code "41") (name "Net-(U1-VREF(DAC))") (class "Default")
      (node (ref "C12") (pin "1") (pinfunction "1_1") (pintype "passive"))
      (node (ref "C9") (pin "1") (pinfunction "1_1") (pintype "passive"))
      (node (ref "U1") (pin "12") (pinfunction "VREF(DAC)_12") (pintype "output"))
    )
    (net (code "42") (name "Net-(U2-CPN)") (class "Default")
      (node (ref "C21") (pin "1") (pinfunction "1_1") (pintype "passive"))
      (node (ref "U2") (pin "9") (pinfunction "CPN_9") (pintype "power_in"))
    )
    (net (code "43") (name "Net-(U2-CPP)") (class "Default")
      (node (ref "C21") (pin "2") (pinfunction "2_2") (pintype "passive"))
      (node (ref "U2") (pin "11") (pinfunction "CPP_11") (pintype "power_in"))
    )
    (net (code "44") (name "Net-(U2-EN)") (class "Default")
      (node (ref "R17") (pin "1") (pinfunction "1_1") (pintype "passive"))
      (node (ref "U2") (pin "13") (pinfunction "EN_13") (pintype "input"))
    )
    (net (code "45") (name "Net-(U2-HPVDD)") (class "Default")
      (node (ref "C19") (pin "1") (pinfunction "1_1") (pintype "passive"))
      (node (ref "U2") (pin "12") (pinfunction "HPVDD_12") (pintype "power_in"))
    )
    (net (code "46") (name "Net-(U2-HPVSS)") (class "Default")
      (node (ref "C22") (pin "1") (pinfunction "1_1") (pintype "passive"))
      (node (ref "U2") (pin "8") (pinfunction "HPVSS_8") (pintype "power_in"))
    )
    (net (code "47") (name "Net-(U2-INL-)") (class "Default")
      (node (ref "C17") (pin "2") (pinfunction "2_2") (pintype "passive"))
      (node (ref "U2") (pin "1") (pinfunction "INL-_1") (pintype "input"))
    )
    (net (code "48") (name "Net-(U2-INR-)") (class "Default")
      (node (ref "C18") (pin "2") (pinfunction "2_2") (pintype "passive"))
      (node (ref "U2") (pin "4") (pinfunction "INR-_4") (pintype "input"))
    )
    (net (code "49") (name "Net-(U2-OUTL)") (class "Default")
      (node (ref "U2") (pin "16") (pinfunction "OUTL_16") (pintype "output"))
      (node (ref "X1") (pin "5") (pinfunction "5_5") (pintype "passive"))
    )
    (net (code "50") (name "Net-(U2-OUTR)") (class "Default")
      (node (ref "R18") (pin "1") (pinfunction "1_1") (pintype "passive"))
      (node (ref "U2") (pin "5") (pinfunction "OUTR_5") (pintype "output"))
      (node (ref "X1") (pin "2") (pinfunction "2_2") (pintype "passive"))
    )
    (net (code "51") (name "Net-(U4-A)") (class "Default")
      (node (ref "C24") (pin "1") (pinfunction "1_1") (pintype "passive"))
      (node (ref "R20") (pin "2") (pinfunction "2_2") (pintype "passive"))
      (node (ref "U4") (pin "2") (pinfunction "A_2") (pintype "input"))
    )
    (net (code "52") (name "Net-(U5-INL+)") (class "Default")
      (node (ref "C25") (pin "1") (pinfunction "1_1") (pintype "passive"))
      (node (ref "U5") (pin "P$3") (pinfunction "INL+_P$3") (pintype "input"))
    )
    (net (code "53") (name "Net-(U5-INL-)") (class "Default")
      (node (ref "C26") (pin "1") (pinfunction "1_1") (pintype "passive"))
      (node (ref "U5") (pin "P$4") (pinfunction "INL-_P$4") (pintype "input"))
    )
    (net (code "54") (name "Net-(U5-INR+)") (class "Default")
      (node (ref "C27") (pin "1") (pinfunction "1_1") (pintype "passive"))
      (node (ref "U5") (pin "P$7") (pinfunction "INR+_P$7") (pintype "input"))
    )
    (net (code "55") (name "Net-(U5-INR-)") (class "Default")
      (node (ref "C28") (pin "1") (pinfunction "1_1") (pintype "passive"))
      (node (ref "U5") (pin "P$6") (pinfunction "INR-_P$6") (pintype "input"))
    )
    (net (code "56") (name "Net-(U5-OUTL+)") (class "Default")
      (node (ref "J5") (pin "1") (pinfunction "1_1") (pintype "passive"))
      (node (ref "U5") (pin "P$13") (pinfunction "OUTL+_P$13") (pintype "output"))
    )
    (net (code "57") (name "Net-(U5-OUTL-)") (class "Default")
      (node (ref "J5") (pin "2") (pinfunction "2_2") (pintype "passive"))
      (node (ref "U5") (pin "P$14") (pinfunction "OUTL-_P$14") (pintype "output"))
    )
    (net (code "58") (name "Net-(U5-OUTR+)") (class "Default")
      (node (ref "J6") (pin "1") (pinfunction "1_1") (pintype "passive"))
      (node (ref "U5") (pin "P$10") (pinfunction "OUTR+_P$10") (pintype "output"))
    )
    (net (code "59") (name "Net-(U5-OUTR-)") (class "Default")
      (node (ref "J6") (pin "2") (pinfunction "2_2") (pintype "passive"))
      (node (ref "U5") (pin "P$9") (pinfunction "OUTR-_P$9") (pintype "output"))
    )
    (net (code "60") (name "P0") (class "Default")
      (node (ref "J4") (pin "1") (pinfunction "1_1") (pintype "passive"))
      (node (ref "U6") (pin "5") (pinfunction "P0_5") (pintype "bidirectional"))
    )
    (net (code "61") (name "P1") (class "Default")
      (node (ref "J4") (pin "2") (pinfunction "2_2") (pintype "passive"))
      (node (ref "U6") (pin "6") (pinfunction "P1_6") (pintype "bidirectional"))
    )
    (net (code "62") (name "P2") (class "Default")
      (node (ref "J4") (pin "3") (pinfunction "3_3") (pintype "passive"))
      (node (ref "U6") (pin "7") (pinfunction "P2_7") (pintype "bidirectional"))
    )
    (net (code "63") (name "P3") (class "Default")
      (node (ref "J4") (pin "4") (pinfunction "4_4") (pintype "passive"))
      (node (ref "S1") (pin "1") (pinfunction "1_1") (pintype "passive"))
      (node (ref "S1") (pin "2") (pinfunction "1_2") (pintype "passive"))
      (node (ref "U6") (pin "8") (pinfunction "P3_8") (pintype "bidirectional"))
    )
    (net (code "64") (name "P4") (class "Default")
      (node (ref "J4") (pin "5") (pinfunction "5_5") (pintype "passive"))
      (node (ref "S2") (pin "1") (pinfunction "1_1") (pintype "passive"))
      (node (ref "S2") (pin "2") (pinfunction "1_2") (pintype "passive"))
      (node (ref "U6") (pin "10") (pinfunction "P4_10") (pintype "bidirectional"))
    )
    (net (code "65") (name "P5") (class "Default")
      (node (ref "J4") (pin "6") (pinfunction "6_6") (pintype "passive"))
      (node (ref "S3") (pin "1") (pinfunction "1_1") (pintype "passive"))
      (node (ref "S3") (pin "2") (pinfunction "1_2") (pintype "passive"))
      (node (ref "U6") (pin "11") (pinfunction "P5_11") (pintype "bidirectional"))
    )
    (net (code "66") (name "P6") (class "Default")
      (node (ref "J4") (pin "7") (pinfunction "7_7") (pintype "passive"))
      (node (ref "S4") (pin "1") (pinfunction "1_1") (pintype "passive"))
      (node (ref "S4") (pin "2") (pinfunction "1_2") (pintype "passive"))
      (node (ref "U6") (pin "12") (pinfunction "P6_12") (pintype "bidirectional"))
    )
    (net (code "67") (name "P7") (class "Default")
      (node (ref "J4") (pin "8") (pinfunction "8_8") (pintype "passive"))
      (node (ref "S5") (pin "1") (pinfunction "1_1") (pintype "passive"))
      (node (ref "S5") (pin "2") (pinfunction "1_2") (pintype "passive"))
      (node (ref "U6") (pin "13") (pinfunction "P7_13") (pintype "bidirectional"))
    )
    (net (code "68") (name "RESET") (class "Default")
      (node (ref "J2") (pin "9") (pinfunction "9_9") (pintype "passive"))
      (node (ref "S6") (pin "1") (pinfunction "1_1") (pintype "passive"))
      (node (ref "S6") (pin "2") (pinfunction "1_2") (pintype "passive"))
    )
    (net (code "69") (name "SCK") (class "Default")
      (node (ref "J2") (pin "3") (pinfunction "3_3") (pintype "passive"))
      (node (ref "J7") (pin "3") (pinfunction "3_3") (pintype "passive"))
      (node (ref "LED1") (pin "A") (pinfunction "A_A") (pintype "passive"))
      (node (ref "SD1") (pin "SCK") (pinfunction "SCK_SCK") (pintype "bidirectional"))
    )
    (net (code "70") (name "SCL") (class "Default")
      (node (ref "J2") (pin "8") (pinfunction "8_8") (pintype "passive"))
      (node (ref "J7") (pin "7") (pinfunction "7_7") (pintype "passive"))
      (node (ref "R27") (pin "1") (pinfunction "1_1") (pintype "passive"))
      (node (ref "U6") (pin "15") (pinfunction "SCL_15") (pintype "bidirectional"))
    )
    (net (code "71") (name "SDA") (class "Default")
      (node (ref "J2") (pin "7") (pinfunction "7_7") (pintype "passive"))
      (node (ref "J7") (pin "6") (pinfunction "6_6") (pintype "passive"))
      (node (ref "R28") (pin "1") (pinfunction "1_1") (pintype "passive"))
      (node (ref "U6") (pin "16") (pinfunction "SDA_16") (pintype "bidirectional"))
    )
    (net (code "72") (name "SD_CS") (class "Default")
      (node (ref "J2") (pin "4") (pinfunction "4_4") (pintype "passive"))
      (node (ref "R15") (pin "1") (pinfunction "1_1") (pintype "passive"))
      (node (ref "R16") (pin "1") (pinfunction "1_1") (pintype "passive"))
      (node (ref "SD1") (pin "CS") (pinfunction "~{CS}_CS") (pintype "bidirectional"))
    )
    (net (code "73") (name "unconnected-(SD1-PadDAT1)") (class "Default")
      (node (ref "SD1") (pin "DAT1") (pinfunction "DAT1_DAT1") (pintype "bidirectional"))
    )
    (net (code "74") (name "unconnected-(SD1-PadDAT2)") (class "Default")
      (node (ref "SD1") (pin "DAT2") (pinfunction "DAT2_DAT2") (pintype "bidirectional"))
    )
    (net (code "75") (name "unconnected-(SD1-PadSW1)") (class "Default")
      (node (ref "SD1") (pin "SW1") (pinfunction "SW1_SW1") (pintype "bidirectional"))
    )
    (net (code "76") (name "unconnected-(SD1-PadSW2)") (class "Default")
      (node (ref "SD1") (pin "SW2") (pinfunction "SW2_SW2") (pintype "bidirectional"))
    )
    (net (code "77") (name "unconnected-(U4-NC-Pad1)") (class "Default")
      (node (ref "U4") (pin "1") (pinfunction "NC_1") (pintype "no_connect"))
    )
    (net (code "78") (name "unconnected-(U4-NC-Pad5)") (class "Default")
      (node (ref "U4") (pin "5") (pinfunction "NC_5") (pintype "no_connect"))
    )
    (net (code "79") (name "unconnected-(U6-INT-Pad14)") (class "Default")
      (node (ref "U6") (pin "14") (pinfunction "INT_14") (pintype "bidirectional"))
    )
    (net (code "80") (name "unconnected-(X1-Pad4)") (class "Default")
      (node (ref "X1") (pin "4") (pinfunction "4_4") (pintype "passive"))
    )
  )
)
